# Sheet2.net
KiCad netlist of a schematic drawn in Altium Designer
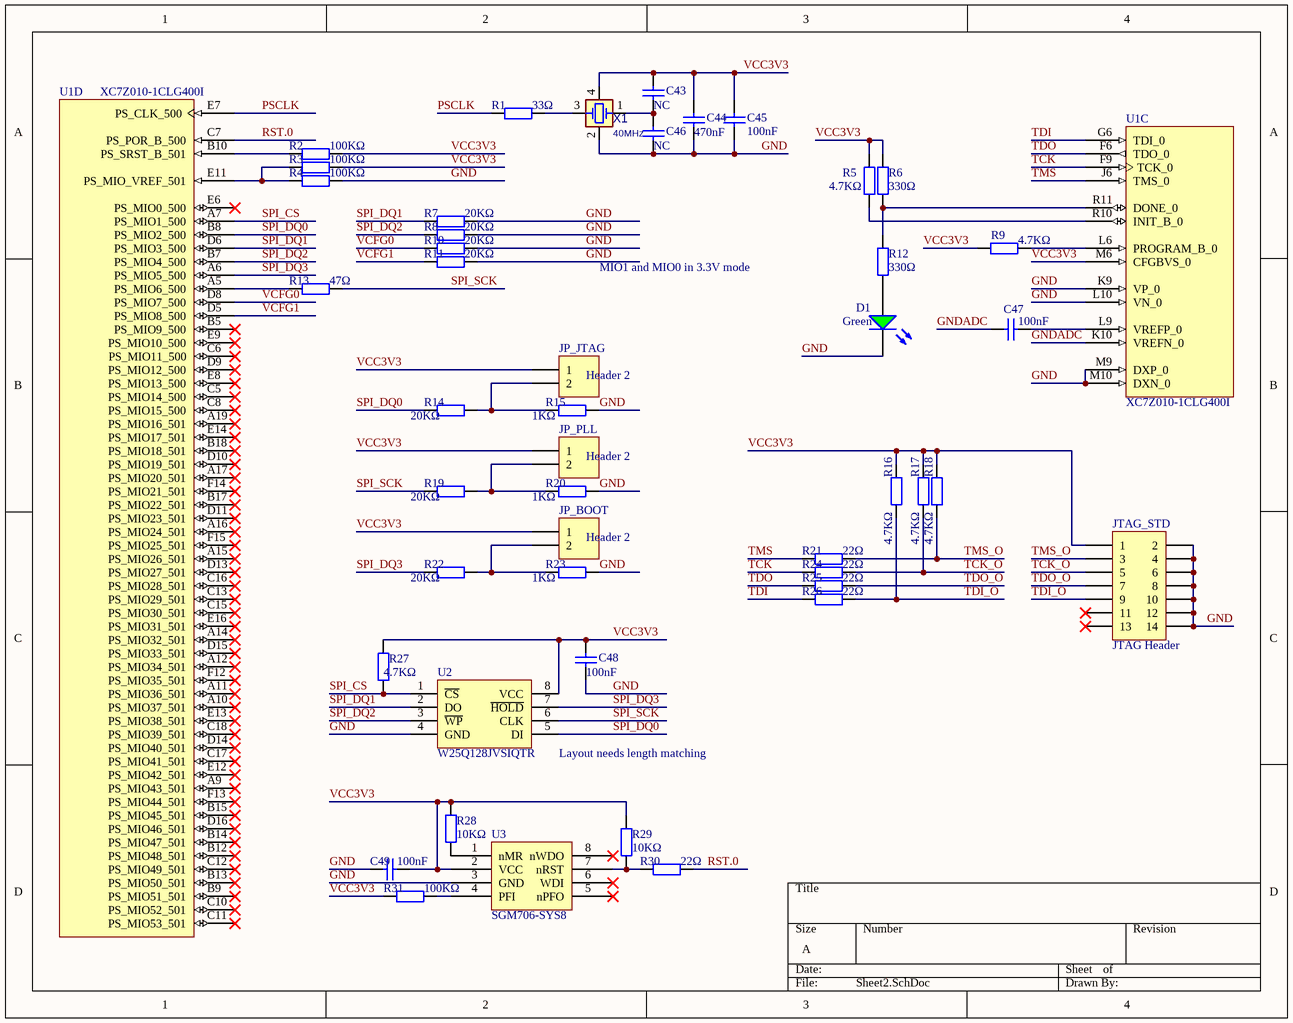
[diagram p0: Sheet2.SchDoc]

(export (version "E")
  (design (tool "Eeschema 10.0.6"))
  (components
    (comp (ref "C43")
      (value "NC")
      (footprint "0402_C")
      (description "贴片电容")
      (libsource (lib "Cap") (part "0402 470nF (474) 10% 10V"))
    )
    (comp (ref "C44")
      (value "470nF")
      (footprint "0402_C")
      (description "贴片电容")
      (libsource (lib "Cap") (part "0402 470nF (474) 10% 10V"))
    )
    (comp (ref "C45")
      (value "100nF")
      (footprint "1206_C")
      (description "贴片电容")
      (libsource (lib "Cap") (part "1206 100nF (104) 10% 50V"))
    )
    (comp (ref "C46")
      (value "NC")
      (footprint "0402_C")
      (description "贴片电容")
      (libsource (lib "Cap") (part "0402 470nF (474) 10% 10V"))
    )
    (comp (ref "C47")
      (value "100nF")
      (footprint "1206_C")
      (description "贴片电容")
      (libsource (lib "Cap") (part "1206 100nF (104) 10% 50V"))
    )
    (comp (ref "C48")
      (value "100nF")
      (footprint "1206_C")
      (description "贴片电容")
      (libsource (lib "Cap") (part "1206 100nF (104) 10% 50V"))
    )
    (comp (ref "C49")
      (value "100nF")
      (footprint "1206_C")
      (description "贴片电容")
      (libsource (lib "Cap") (part "1206 100nF (104) 10% 50V"))
    )
    (comp (ref "D1")
      (value "Green")
      (footprint "0805_LED_S1")
      (description "发光二极管")
      (libsource (lib "LED") (part "0805 翠绿"))
    )
    (comp (ref "JP_BOOT")
      (value "Header 2")
      (footprint "HDR1X2")
      (description "Header, 2-Pin")
      (fields (field (name "PUBLISHER") "Altium Limited"))
      (libsource (lib "Miscellaneous Connectors") (part "Header 2"))
    )
    (comp (ref "JP_JTAG")
      (value "Header 2")
      (footprint "HDR1X2")
      (description "Header, 2-Pin")
      (fields (field (name "PUBLISHER") "Altium Limited"))
      (libsource (lib "Miscellaneous Connectors") (part "Header 2"))
    )
    (comp (ref "JP_PLL")
      (value "Header 2")
      (footprint "HDR1X2")
      (description "Header, 2-Pin")
      (fields (field (name "PUBLISHER") "Altium Limited"))
      (libsource (lib "Miscellaneous Connectors") (part "Header 2"))
    )
    (comp (ref "JTAG_STD")
      (value "JTAG Header")
      (footprint "HDR2X7")
      (description "Header, 7-Pin, Dual row")
      (fields (field (name "PUBLISHER") "Altium Limited"))
      (libsource (lib "Miscellaneous Connectors") (part "Header 7X2"))
    )
    (comp (ref "R1")
      (value "33Ω")
      (footprint "0603_R")
      (description "贴片电阻")
      (libsource (lib "RES") (part "0603 33Ω (33R0) 1%"))
    )
    (comp (ref "R2")
      (value "100KΩ")
      (footprint "1206_R")
      (description "贴片电阻")
      (libsource (lib "RES") (part "1206 100KΩ (1003) 1%"))
    )
    (comp (ref "R3")
      (value "100KΩ")
      (footprint "1206_R")
      (description "贴片电阻")
      (libsource (lib "RES") (part "1206 100KΩ (1003) 1%"))
    )
    (comp (ref "R4")
      (value "100KΩ")
      (footprint "1206_R")
      (description "贴片电阻")
      (libsource (lib "RES") (part "1206 100KΩ (1003) 1%"))
    )
    (comp (ref "R5")
      (value "4.7KΩ")
      (footprint "1206_R")
      (description "贴片电阻")
      (libsource (lib "RES") (part "1206 4.7KΩ (4701) 1%"))
    )
    (comp (ref "R6")
      (value "330Ω")
      (footprint "0805_R")
      (description "贴片电阻")
      (libsource (lib "RES") (part "0805 330Ω (3300) 1%"))
    )
    (comp (ref "R7")
      (value "20KΩ")
      (footprint "0805_R")
      (description "贴片电阻")
      (libsource (lib "RES") (part "0805 20KΩ (2002) 1%"))
    )
    (comp (ref "R8")
      (value "20KΩ")
      (footprint "0805_R")
      (description "贴片电阻")
      (libsource (lib "RES") (part "0805 20KΩ (2002) 1%"))
    )
    (comp (ref "R9")
      (value "4.7KΩ")
      (footprint "1206_R")
      (description "贴片电阻")
      (libsource (lib "") (part "1206 4.7KΩ (4701) 1%_1"))
    )
    (comp (ref "R10")
      (value "20KΩ")
      (footprint "0805_R")
      (description "贴片电阻")
      (libsource (lib "RES") (part "0805 20KΩ (2002) 1%"))
    )
    (comp (ref "R11")
      (value "20KΩ")
      (footprint "0805_R")
      (description "贴片电阻")
      (libsource (lib "RES") (part "0805 20KΩ (2002) 1%"))
    )
    (comp (ref "R12")
      (value "330Ω")
      (footprint "0805_R")
      (description "贴片电阻")
      (libsource (lib "") (part "0805 330Ω (3300) 1%_1"))
    )
    (comp (ref "R13")
      (value "47Ω")
      (footprint "0805_R")
      (description "贴片电阻")
      (libsource (lib "RES") (part "0805 47Ω (47R0) 1%"))
    )
    (comp (ref "R14")
      (value "20KΩ")
      (footprint "0805_R")
      (description "贴片电阻")
      (libsource (lib "RES") (part "0805 20KΩ (2002) 1%"))
    )
    (comp (ref "R15")
      (value "1KΩ")
      (footprint "1206_R")
      (description "贴片电阻")
      (libsource (lib "RES") (part "1206 1KΩ (1001) 1%"))
    )
    (comp (ref "R16")
      (value "4.7KΩ")
      (footprint "1206_R")
      (description "贴片电阻")
      (libsource (lib "RES") (part "1206 4.7KΩ (4701) 1%"))
    )
    (comp (ref "R17")
      (value "4.7KΩ")
      (footprint "1206_R")
      (description "贴片电阻")
      (libsource (lib "RES") (part "1206 4.7KΩ (4701) 1%"))
    )
    (comp (ref "R18")
      (value "4.7KΩ")
      (footprint "1206_R")
      (description "贴片电阻")
      (libsource (lib "RES") (part "1206 4.7KΩ (4701) 1%"))
    )
    (comp (ref "R19")
      (value "20KΩ")
      (footprint "0805_R")
      (description "贴片电阻")
      (libsource (lib "RES") (part "0805 20KΩ (2002) 1%"))
    )
    (comp (ref "R20")
      (value "1KΩ")
      (footprint "1206_R")
      (description "贴片电阻")
      (libsource (lib "RES") (part "1206 1KΩ (1001) 1%"))
    )
    (comp (ref "R21")
      (value "22Ω")
      (footprint "1206_R")
      (description "贴片电阻")
      (libsource (lib "RES") (part "1206 22Ω (22R0) 1%"))
    )
    (comp (ref "R22")
      (value "20KΩ")
      (footprint "0805_R")
      (description "贴片电阻")
      (libsource (lib "RES") (part "0805 20KΩ (2002) 1%"))
    )
    (comp (ref "R23")
      (value "1KΩ")
      (footprint "1206_R")
      (description "贴片电阻")
      (libsource (lib "RES") (part "1206 1KΩ (1001) 1%"))
    )
    (comp (ref "R24")
      (value "22Ω")
      (footprint "1206_R")
      (description "贴片电阻")
      (libsource (lib "RES") (part "1206 22Ω (22R0) 1%"))
    )
    (comp (ref "R25")
      (value "22Ω")
      (footprint "1206_R")
      (description "贴片电阻")
      (libsource (lib "RES") (part "1206 22Ω (22R0) 1%"))
    )
    (comp (ref "R26")
      (value "22Ω")
      (footprint "1206_R")
      (description "贴片电阻")
      (libsource (lib "RES") (part "1206 22Ω (22R0) 1%"))
    )
    (comp (ref "R27")
      (value "4.7KΩ")
      (footprint "1206_R")
      (description "贴片电阻")
      (libsource (lib "RES") (part "1206 4.7KΩ (4701) 1%"))
    )
    (comp (ref "R28")
      (value "10KΩ")
      (footprint "1206_R")
      (description "贴片电阻")
      (libsource (lib "RES") (part "1206 10KΩ (1002) 1%"))
    )
    (comp (ref "R29")
      (value "10KΩ")
      (footprint "1206_R")
      (description "贴片电阻")
      (libsource (lib "RES") (part "1206 10KΩ (1002) 1%"))
    )
    (comp (ref "R30")
      (value "22Ω")
      (footprint "1206_R")
      (description "贴片电阻")
      (libsource (lib "RES") (part "1206 22Ω (22R0) 1%"))
    )
    (comp (ref "R31")
      (value "100KΩ")
      (footprint "1206_R")
      (description "贴片电阻")
      (libsource (lib "RES") (part "1206 100KΩ (1003) 1%"))
    )
    (comp (ref "U1")
      (value "XC7Z010-1CLG400I")
      (footprint "CLG400")
      (fields (field (name "GENERIC PART NUMBER") "XC7Z010") (field (name "MANUFACTURER") "Xilinx"))
      (libsource (lib "Xilinx Zynq-7000") (part "XC7Z010-1CLG400I"))
    )
    (comp (ref "U2")
      (value "W25Q128JVSIQTR")
      (footprint "SOIC-8_208mil")
      (description "Flash ROM")
      (libsource (lib "IC") (part "W25Q128JVSIQTR_[C97521]"))
    )
    (comp (ref "U3")
      (value "SGM706-SYS8")
      (footprint "SOIC-8_150mil")
      (description "MCU  Supervisor, 150mil SOP-8")
      (libsource (lib "IC") (part "EEPROM/AT24C256C-SSHL-T_[C6482]"))
    )
    (comp (ref "X1")
      (value "40MHz")
      (footprint "XTL_4_3225")
      (description "CRYSTAL 40.00 MHZ 4pF, 10PPM")
      (fields (field (name "MANF") "ABRACON") (field (name "MANF_P#") "ABM8W-40.0000MHZ-4-B1U-T3"))
      (libsource (lib "Crystal Oscillator") (part "XTL_4_40MHz_3225A"))
    )
  )
  (nets
    (net (code "1") (name "/GND") (class "Default")
      (node (ref "C44") (pin "2") (pinfunction "2_2") (pintype "passive"))
      (node (ref "C45") (pin "1") (pinfunction "1_1") (pintype "passive"))
      (node (ref "C46") (pin "2") (pinfunction "2_2") (pintype "passive"))
      (node (ref "C48") (pin "1") (pinfunction "1_1") (pintype "passive"))
      (node (ref "C49") (pin "1") (pinfunction "1_1") (pintype "passive"))
      (node (ref "D1") (pin "K") (pinfunction "K_K") (pintype "passive"))
      (node (ref "JTAG_STD") (pin "10") (pinfunction "10_10") (pintype "passive"))
      (node (ref "JTAG_STD") (pin "12") (pinfunction "12_12") (pintype "passive"))
      (node (ref "JTAG_STD") (pin "14") (pinfunction "14_14") (pintype "passive"))
      (node (ref "JTAG_STD") (pin "2") (pinfunction "2_2") (pintype "passive"))
      (node (ref "JTAG_STD") (pin "4") (pinfunction "4_4") (pintype "passive"))
      (node (ref "JTAG_STD") (pin "6") (pinfunction "6_6") (pintype "passive"))
      (node (ref "JTAG_STD") (pin "8") (pinfunction "8_8") (pintype "passive"))
      (node (ref "R10") (pin "2") (pinfunction "2_2") (pintype "passive"))
      (node (ref "R11") (pin "2") (pinfunction "2_2") (pintype "passive"))
      (node (ref "R15") (pin "2") (pinfunction "2_2") (pintype "passive"))
      (node (ref "R20") (pin "2") (pinfunction "2_2") (pintype "passive"))
      (node (ref "R23") (pin "2") (pinfunction "2_2") (pintype "passive"))
      (node (ref "R4") (pin "2") (pinfunction "2_2") (pintype "passive"))
      (node (ref "R7") (pin "2") (pinfunction "2_2") (pintype "passive"))
      (node (ref "R8") (pin "2") (pinfunction "2_2") (pintype "passive"))
      (node (ref "U1") (pin "K9") (pinfunction "VP_0_K9") (pintype "input"))
      (node (ref "U1") (pin "L10") (pinfunction "VN_0_L10") (pintype "input"))
      (node (ref "U1") (pin "M10") (pinfunction "DXN_0_M10") (pintype "input"))
      (node (ref "U1") (pin "M9") (pinfunction "DXP_0_M9") (pintype "input"))
      (node (ref "U2") (pin "4") (pinfunction "GND_4") (pintype "passive"))
      (node (ref "U3") (pin "3") (pinfunction "GND_3") (pintype "passive"))
      (node (ref "X1") (pin "2") (pinfunction "GND1_2") (pintype "passive"))
    )
    (net (code "2") (name "/GNDADC") (class "Default")
      (node (ref "C47") (pin "1") (pinfunction "1_1") (pintype "passive"))
      (node (ref "U1") (pin "K10") (pinfunction "VREFN_0_K10") (pintype "input"))
    )
    (net (code "3") (name "/PSCLK") (class "Default")
      (node (ref "R1") (pin "1") (pinfunction "1_1") (pintype "passive"))
      (node (ref "U1") (pin "E7") (pinfunction "PS_CLK_500_E7") (pintype "input"))
    )
    (net (code "4") (name "/RST.0") (class "Default")
      (node (ref "R30") (pin "2") (pinfunction "2_2") (pintype "passive"))
      (node (ref "U1") (pin "C7") (pinfunction "PS_POR_B_500_C7") (pintype "input"))
    )
    (net (code "5") (name "/SPI_CS") (class "Default")
      (node (ref "R27") (pin "1") (pinfunction "1_1") (pintype "passive"))
      (node (ref "U1") (pin "A7") (pinfunction "PS_MIO1_500_A7") (pintype "bidirectional"))
      (node (ref "U2") (pin "1") (pinfunction "~{CS}_1") (pintype "passive"))
    )
    (net (code "6") (name "/SPI_DQ0") (class "Default")
      (node (ref "R14") (pin "1") (pinfunction "1_1") (pintype "passive"))
      (node (ref "U1") (pin "B8") (pinfunction "PS_MIO2_500_B8") (pintype "bidirectional"))
      (node (ref "U2") (pin "5") (pinfunction "DI_5") (pintype "passive"))
    )
    (net (code "7") (name "/SPI_DQ1") (class "Default")
      (node (ref "R7") (pin "1") (pinfunction "1_1") (pintype "passive"))
      (node (ref "U1") (pin "D6") (pinfunction "PS_MIO3_500_D6") (pintype "bidirectional"))
      (node (ref "U2") (pin "2") (pinfunction "DO_2") (pintype "passive"))
    )
    (net (code "8") (name "/SPI_DQ2") (class "Default")
      (node (ref "R8") (pin "1") (pinfunction "1_1") (pintype "passive"))
      (node (ref "U1") (pin "B7") (pinfunction "PS_MIO4_500_B7") (pintype "bidirectional"))
      (node (ref "U2") (pin "3") (pinfunction "~{WP}_3") (pintype "passive"))
    )
    (net (code "9") (name "/SPI_DQ3") (class "Default")
      (node (ref "R22") (pin "1") (pinfunction "1_1") (pintype "passive"))
      (node (ref "U1") (pin "A6") (pinfunction "PS_MIO5_500_A6") (pintype "bidirectional"))
      (node (ref "U2") (pin "7") (pinfunction "~{HOLD}_7") (pintype "passive"))
    )
    (net (code "10") (name "/SPI_SCK") (class "Default")
      (node (ref "R13") (pin "2") (pinfunction "2_2") (pintype "passive"))
      (node (ref "R19") (pin "1") (pinfunction "1_1") (pintype "passive"))
      (node (ref "U2") (pin "6") (pinfunction "CLK_6") (pintype "passive"))
    )
    (net (code "11") (name "/TCK") (class "Default")
      (node (ref "R24") (pin "1") (pinfunction "1_1") (pintype "passive"))
      (node (ref "U1") (pin "F9") (pinfunction "TCK_0_F9") (pintype "input"))
    )
    (net (code "12") (name "/TCK_O") (class "Default")
      (node (ref "JTAG_STD") (pin "5") (pinfunction "5_5") (pintype "passive"))
      (node (ref "R17") (pin "1") (pinfunction "1_1") (pintype "passive"))
      (node (ref "R24") (pin "2") (pinfunction "2_2") (pintype "passive"))
    )
    (net (code "13") (name "/TDI") (class "Default")
      (node (ref "R26") (pin "1") (pinfunction "1_1") (pintype "passive"))
      (node (ref "U1") (pin "G6") (pinfunction "TDI_0_G6") (pintype "input"))
    )
    (net (code "14") (name "/TDI_O") (class "Default")
      (node (ref "JTAG_STD") (pin "9") (pinfunction "9_9") (pintype "passive"))
      (node (ref "R16") (pin "1") (pinfunction "1_1") (pintype "passive"))
      (node (ref "R26") (pin "2") (pinfunction "2_2") (pintype "passive"))
    )
    (net (code "15") (name "/TDO") (class "Default")
      (node (ref "R25") (pin "1") (pinfunction "1_1") (pintype "passive"))
      (node (ref "U1") (pin "F6") (pinfunction "TDO_0_F6") (pintype "output"))
    )
    (net (code "16") (name "/TDO_O") (class "Default")
      (node (ref "JTAG_STD") (pin "7") (pinfunction "7_7") (pintype "passive"))
      (node (ref "R25") (pin "2") (pinfunction "2_2") (pintype "passive"))
    )
    (net (code "17") (name "/TMS") (class "Default")
      (node (ref "R21") (pin "1") (pinfunction "1_1") (pintype "passive"))
      (node (ref "U1") (pin "J6") (pinfunction "TMS_0_J6") (pintype "input"))
    )
    (net (code "18") (name "/TMS_O") (class "Default")
      (node (ref "JTAG_STD") (pin "3") (pinfunction "3_3") (pintype "passive"))
      (node (ref "R18") (pin "1") (pinfunction "1_1") (pintype "passive"))
      (node (ref "R21") (pin "2") (pinfunction "2_2") (pintype "passive"))
    )
    (net (code "19") (name "/VCC3V3") (class "Default")
      (node (ref "C43") (pin "1") (pinfunction "1_1") (pintype "passive"))
      (node (ref "C44") (pin "1") (pinfunction "1_1") (pintype "passive"))
      (node (ref "C45") (pin "2") (pinfunction "2_2") (pintype "passive"))
      (node (ref "C48") (pin "2") (pinfunction "2_2") (pintype "passive"))
      (node (ref "C49") (pin "2") (pinfunction "2_2") (pintype "passive"))
      (node (ref "JP_BOOT") (pin "1") (pinfunction "1_1") (pintype "passive"))
      (node (ref "JP_JTAG") (pin "1") (pinfunction "1_1") (pintype "passive"))
      (node (ref "JP_PLL") (pin "1") (pinfunction "1_1") (pintype "passive"))
      (node (ref "JTAG_STD") (pin "1") (pinfunction "1_1") (pintype "passive"))
      (node (ref "R16") (pin "2") (pinfunction "2_2") (pintype "passive"))
      (node (ref "R17") (pin "2") (pinfunction "2_2") (pintype "passive"))
      (node (ref "R18") (pin "2") (pinfunction "2_2") (pintype "passive"))
      (node (ref "R2") (pin "2") (pinfunction "2_2") (pintype "passive"))
      (node (ref "R27") (pin "2") (pinfunction "2_2") (pintype "passive"))
      (node (ref "R28") (pin "2") (pinfunction "2_2") (pintype "passive"))
      (node (ref "R29") (pin "2") (pinfunction "2_2") (pintype "passive"))
      (node (ref "R3") (pin "2") (pinfunction "2_2") (pintype "passive"))
      (node (ref "R31") (pin "1") (pinfunction "1_1") (pintype "passive"))
      (node (ref "R5") (pin "2") (pinfunction "2_2") (pintype "passive"))
      (node (ref "R6") (pin "1") (pinfunction "1_1") (pintype "passive"))
      (node (ref "R9") (pin "1") (pinfunction "1_1") (pintype "passive"))
      (node (ref "U1") (pin "M6") (pinfunction "CFGBVS_0_M6") (pintype "input"))
      (node (ref "U2") (pin "8") (pinfunction "VCC_8") (pintype "passive"))
      (node (ref "U3") (pin "2") (pinfunction "VCC_2") (pintype "passive"))
      (node (ref "X1") (pin "4") (pinfunction "GND2_4") (pintype "passive"))
    )
    (net (code "20") (name "/VCFG0") (class "Default")
      (node (ref "R10") (pin "1") (pinfunction "1_1") (pintype "passive"))
      (node (ref "U1") (pin "D8") (pinfunction "PS_MIO7_500_D8") (pintype "bidirectional"))
    )
    (net (code "21") (name "/VCFG1") (class "Default")
      (node (ref "R11") (pin "1") (pinfunction "1_1") (pintype "passive"))
      (node (ref "U1") (pin "D5") (pinfunction "PS_MIO8_500_D5") (pintype "bidirectional"))
    )
    (net (code "22") (name "Net-(D1-PadA)") (class "Default")
      (node (ref "D1") (pin "A") (pinfunction "A_A") (pintype "passive"))
      (node (ref "R12") (pin "1") (pinfunction "1_1") (pintype "passive"))
    )
    (net (code "23") (name "Net-(JP_BOOT-Pad2)") (class "Default")
      (node (ref "JP_BOOT") (pin "2") (pinfunction "2_2") (pintype "passive"))
      (node (ref "R22") (pin "2") (pinfunction "2_2") (pintype "passive"))
      (node (ref "R23") (pin "1") (pinfunction "1_1") (pintype "passive"))
    )
    (net (code "24") (name "Net-(JP_JTAG-Pad2)") (class "Default")
      (node (ref "JP_JTAG") (pin "2") (pinfunction "2_2") (pintype "passive"))
      (node (ref "R14") (pin "2") (pinfunction "2_2") (pintype "passive"))
      (node (ref "R15") (pin "1") (pinfunction "1_1") (pintype "passive"))
    )
    (net (code "25") (name "Net-(JP_PLL-Pad2)") (class "Default")
      (node (ref "JP_PLL") (pin "2") (pinfunction "2_2") (pintype "passive"))
      (node (ref "R19") (pin "2") (pinfunction "2_2") (pintype "passive"))
      (node (ref "R20") (pin "1") (pinfunction "1_1") (pintype "passive"))
    )
    (net (code "26") (name "Net-(U1C-DONE_0)") (class "Default")
      (node (ref "R12") (pin "2") (pinfunction "2_2") (pintype "passive"))
      (node (ref "R6") (pin "2") (pinfunction "2_2") (pintype "passive"))
      (node (ref "U1") (pin "R11") (pinfunction "DONE_0_R11") (pintype "bidirectional"))
    )
    (net (code "27") (name "Net-(U1C-INIT_B_0)") (class "Default")
      (node (ref "R5") (pin "1") (pinfunction "1_1") (pintype "passive"))
      (node (ref "U1") (pin "R10") (pinfunction "INIT_B_0_R10") (pintype "bidirectional"))
    )
    (net (code "28") (name "Net-(U1C-PROGRAM_B_0)") (class "Default")
      (node (ref "R9") (pin "2") (pinfunction "2_2") (pintype "passive"))
      (node (ref "U1") (pin "L6") (pinfunction "PROGRAM_B_0_L6") (pintype "input"))
    )
    (net (code "29") (name "Net-(U1C-VREFP_0)") (class "Default")
      (node (ref "C47") (pin "2") (pinfunction "2_2") (pintype "passive"))
      (node (ref "U1") (pin "L9") (pinfunction "VREFP_0_L9") (pintype "input"))
    )
    (net (code "30") (name "Net-(U1D-PS_MIO6_500)") (class "Default")
      (node (ref "R13") (pin "1") (pinfunction "1_1") (pintype "passive"))
      (node (ref "U1") (pin "A5") (pinfunction "PS_MIO6_500_A5") (pintype "bidirectional"))
    )
    (net (code "31") (name "Net-(U1D-PS_MIO_VREF_501)") (class "Default")
      (node (ref "R3") (pin "1") (pinfunction "1_1") (pintype "passive"))
      (node (ref "R4") (pin "1") (pinfunction "1_1") (pintype "passive"))
      (node (ref "U1") (pin "E11") (pinfunction "PS_MIO_VREF_501_E11") (pintype "input"))
    )
    (net (code "32") (name "Net-(U1D-PS_SRST_B_501)") (class "Default")
      (node (ref "R2") (pin "1") (pinfunction "1_1") (pintype "passive"))
      (node (ref "U1") (pin "B10") (pinfunction "PS_SRST_B_501_B10") (pintype "input"))
    )
    (net (code "33") (name "Net-(U3-PFI)") (class "Default")
      (node (ref "R31") (pin "2") (pinfunction "2_2") (pintype "passive"))
      (node (ref "U3") (pin "4") (pinfunction "PFI_4") (pintype "passive"))
    )
    (net (code "34") (name "Net-(U3-nMR)") (class "Default")
      (node (ref "R28") (pin "1") (pinfunction "1_1") (pintype "passive"))
      (node (ref "U3") (pin "1") (pinfunction "nMR_1") (pintype "passive"))
    )
    (net (code "35") (name "Net-(U3-nRST)") (class "Default")
      (node (ref "R29") (pin "1") (pinfunction "1_1") (pintype "passive"))
      (node (ref "R30") (pin "1") (pinfunction "1_1") (pintype "passive"))
      (node (ref "U3") (pin "7") (pinfunction "nRST_7") (pintype "passive"))
    )
    (net (code "36") (name "Net-(X1-XA)") (class "Default")
      (node (ref "C43") (pin "2") (pinfunction "2_2") (pintype "passive"))
      (node (ref "C46") (pin "1") (pinfunction "1_1") (pintype "passive"))
      (node (ref "X1") (pin "1") (pinfunction "XA_1") (pintype "passive"))
    )
    (net (code "37") (name "Net-(X1-XB)") (class "Default")
      (node (ref "R1") (pin "2") (pinfunction "2_2") (pintype "passive"))
      (node (ref "X1") (pin "3") (pinfunction "XB_3") (pintype "passive"))
    )
    (net (code "38") (name "unconnected-(JTAG_STD-Pad11)") (class "Default")
      (node (ref "JTAG_STD") (pin "11") (pinfunction "11_11") (pintype "passive+no_connect"))
    )
    (net (code "39") (name "unconnected-(JTAG_STD-Pad13)") (class "Default")
      (node (ref "JTAG_STD") (pin "13") (pinfunction "13_13") (pintype "passive+no_connect"))
    )
    (net (code "40") (name "unconnected-(U1D-PS_MIO0_500-PadE6)") (class "Default")
      (node (ref "U1") (pin "E6") (pinfunction "PS_MIO0_500_E6") (pintype "bidirectional+no_connect"))
    )
    (net (code "41") (name "unconnected-(U1D-PS_MIO9_500-PadB5)") (class "Default")
      (node (ref "U1") (pin "B5") (pinfunction "PS_MIO9_500_B5") (pintype "bidirectional+no_connect"))
    )
    (net (code "42") (name "unconnected-(U1D-PS_MIO10_500-PadE9)") (class "Default")
      (node (ref "U1") (pin "E9") (pinfunction "PS_MIO10_500_E9") (pintype "bidirectional+no_connect"))
    )
    (net (code "43") (name "unconnected-(U1D-PS_MIO11_500-PadC6)") (class "Default")
      (node (ref "U1") (pin "C6") (pinfunction "PS_MIO11_500_C6") (pintype "bidirectional+no_connect"))
    )
    (net (code "44") (name "unconnected-(U1D-PS_MIO12_500-PadD9)") (class "Default")
      (node (ref "U1") (pin "D9") (pinfunction "PS_MIO12_500_D9") (pintype "bidirectional+no_connect"))
    )
    (net (code "45") (name "unconnected-(U1D-PS_MIO13_500-PadE8)") (class "Default")
      (node (ref "U1") (pin "E8") (pinfunction "PS_MIO13_500_E8") (pintype "bidirectional+no_connect"))
    )
    (net (code "46") (name "unconnected-(U1D-PS_MIO14_500-PadC5)") (class "Default")
      (node (ref "U1") (pin "C5") (pinfunction "PS_MIO14_500_C5") (pintype "bidirectional+no_connect"))
    )
    (net (code "47") (name "unconnected-(U1D-PS_MIO15_500-PadC8)") (class "Default")
      (node (ref "U1") (pin "C8") (pinfunction "PS_MIO15_500_C8") (pintype "bidirectional+no_connect"))
    )
    (net (code "48") (name "unconnected-(U1D-PS_MIO16_501-PadA19)") (class "Default")
      (node (ref "U1") (pin "A19") (pinfunction "PS_MIO16_501_A19") (pintype "bidirectional+no_connect"))
    )
    (net (code "49") (name "unconnected-(U1D-PS_MIO17_501-PadE14)") (class "Default")
      (node (ref "U1") (pin "E14") (pinfunction "PS_MIO17_501_E14") (pintype "bidirectional+no_connect"))
    )
    (net (code "50") (name "unconnected-(U1D-PS_MIO18_501-PadB18)") (class "Default")
      (node (ref "U1") (pin "B18") (pinfunction "PS_MIO18_501_B18") (pintype "bidirectional+no_connect"))
    )
    (net (code "51") (name "unconnected-(U1D-PS_MIO19_501-PadD10)") (class "Default")
      (node (ref "U1") (pin "D10") (pinfunction "PS_MIO19_501_D10") (pintype "bidirectional+no_connect"))
    )
    (net (code "52") (name "unconnected-(U1D-PS_MIO20_501-PadA17)") (class "Default")
      (node (ref "U1") (pin "A17") (pinfunction "PS_MIO20_501_A17") (pintype "bidirectional+no_connect"))
    )
    (net (code "53") (name "unconnected-(U1D-PS_MIO21_501-PadF14)") (class "Default")
      (node (ref "U1") (pin "F14") (pinfunction "PS_MIO21_501_F14") (pintype "bidirectional+no_connect"))
    )
    (net (code "54") (name "unconnected-(U1D-PS_MIO22_501-PadB17)") (class "Default")
      (node (ref "U1") (pin "B17") (pinfunction "PS_MIO22_501_B17") (pintype "bidirectional+no_connect"))
    )
    (net (code "55") (name "unconnected-(U1D-PS_MIO23_501-PadD11)") (class "Default")
      (node (ref "U1") (pin "D11") (pinfunction "PS_MIO23_501_D11") (pintype "bidirectional+no_connect"))
    )
    (net (code "56") (name "unconnected-(U1D-PS_MIO24_501-PadA16)") (class "Default")
      (node (ref "U1") (pin "A16") (pinfunction "PS_MIO24_501_A16") (pintype "bidirectional+no_connect"))
    )
    (net (code "57") (name "unconnected-(U1D-PS_MIO25_501-PadF15)") (class "Default")
      (node (ref "U1") (pin "F15") (pinfunction "PS_MIO25_501_F15") (pintype "bidirectional+no_connect"))
    )
    (net (code "58") (name "unconnected-(U1D-PS_MIO26_501-PadA15)") (class "Default")
      (node (ref "U1") (pin "A15") (pinfunction "PS_MIO26_501_A15") (pintype "bidirectional+no_connect"))
    )
    (net (code "59") (name "unconnected-(U1D-PS_MIO27_501-PadD13)") (class "Default")
      (node (ref "U1") (pin "D13") (pinfunction "PS_MIO27_501_D13") (pintype "bidirectional+no_connect"))
    )
    (net (code "60") (name "unconnected-(U1D-PS_MIO28_501-PadC16)") (class "Default")
      (node (ref "U1") (pin "C16") (pinfunction "PS_MIO28_501_C16") (pintype "bidirectional+no_connect"))
    )
    (net (code "61") (name "unconnected-(U1D-PS_MIO29_501-PadC13)") (class "Default")
      (node (ref "U1") (pin "C13") (pinfunction "PS_MIO29_501_C13") (pintype "bidirectional+no_connect"))
    )
    (net (code "62") (name "unconnected-(U1D-PS_MIO30_501-PadC15)") (class "Default")
      (node (ref "U1") (pin "C15") (pinfunction "PS_MIO30_501_C15") (pintype "bidirectional+no_connect"))
    )
    (net (code "63") (name "unconnected-(U1D-PS_MIO31_501-PadE16)") (class "Default")
      (node (ref "U1") (pin "E16") (pinfunction "PS_MIO31_501_E16") (pintype "bidirectional+no_connect"))
    )
    (net (code "64") (name "unconnected-(U1D-PS_MIO32_501-PadA14)") (class "Default")
      (node (ref "U1") (pin "A14") (pinfunction "PS_MIO32_501_A14") (pintype "bidirectional+no_connect"))
    )
    (net (code "65") (name "unconnected-(U1D-PS_MIO33_501-PadD15)") (class "Default")
      (node (ref "U1") (pin "D15") (pinfunction "PS_MIO33_501_D15") (pintype "bidirectional+no_connect"))
    )
    (net (code "66") (name "unconnected-(U1D-PS_MIO34_501-PadA12)") (class "Default")
      (node (ref "U1") (pin "A12") (pinfunction "PS_MIO34_501_A12") (pintype "bidirectional+no_connect"))
    )
    (net (code "67") (name "unconnected-(U1D-PS_MIO35_501-PadF12)") (class "Default")
      (node (ref "U1") (pin "F12") (pinfunction "PS_MIO35_501_F12") (pintype "bidirectional+no_connect"))
    )
    (net (code "68") (name "unconnected-(U1D-PS_MIO36_501-PadA11)") (class "Default")
      (node (ref "U1") (pin "A11") (pinfunction "PS_MIO36_501_A11") (pintype "bidirectional+no_connect"))
    )
    (net (code "69") (name "unconnected-(U1D-PS_MIO37_501-PadA10)") (class "Default")
      (node (ref "U1") (pin "A10") (pinfunction "PS_MIO37_501_A10") (pintype "bidirectional+no_connect"))
    )
    (net (code "70") (name "unconnected-(U1D-PS_MIO38_501-PadE13)") (class "Default")
      (node (ref "U1") (pin "E13") (pinfunction "PS_MIO38_501_E13") (pintype "bidirectional+no_connect"))
    )
    (net (code "71") (name "unconnected-(U1D-PS_MIO39_501-PadC18)") (class "Default")
      (node (ref "U1") (pin "C18") (pinfunction "PS_MIO39_501_C18") (pintype "bidirectional+no_connect"))
    )
    (net (code "72") (name "unconnected-(U1D-PS_MIO40_501-PadD14)") (class "Default")
      (node (ref "U1") (pin "D14") (pinfunction "PS_MIO40_501_D14") (pintype "bidirectional+no_connect"))
    )
    (net (code "73") (name "unconnected-(U1D-PS_MIO41_501-PadC17)") (class "Default")
      (node (ref "U1") (pin "C17") (pinfunction "PS_MIO41_501_C17") (pintype "bidirectional+no_connect"))
    )
    (net (code "74") (name "unconnected-(U1D-PS_MIO42_501-PadE12)") (class "Default")
      (node (ref "U1") (pin "E12") (pinfunction "PS_MIO42_501_E12") (pintype "bidirectional+no_connect"))
    )
    (net (code "75") (name "unconnected-(U1D-PS_MIO43_501-PadA9)") (class "Default")
      (node (ref "U1") (pin "A9") (pinfunction "PS_MIO43_501_A9") (pintype "bidirectional+no_connect"))
    )
    (net (code "76") (name "unconnected-(U1D-PS_MIO44_501-PadF13)") (class "Default")
      (node (ref "U1") (pin "F13") (pinfunction "PS_MIO44_501_F13") (pintype "bidirectional+no_connect"))
    )
    (net (code "77") (name "unconnected-(U1D-PS_MIO45_501-PadB15)") (class "Default")
      (node (ref "U1") (pin "B15") (pinfunction "PS_MIO45_501_B15") (pintype "bidirectional+no_connect"))
    )
    (net (code "78") (name "unconnected-(U1D-PS_MIO46_501-PadD16)") (class "Default")
      (node (ref "U1") (pin "D16") (pinfunction "PS_MIO46_501_D16") (pintype "bidirectional+no_connect"))
    )
    (net (code "79") (name "unconnected-(U1D-PS_MIO47_501-PadB14)") (class "Default")
      (node (ref "U1") (pin "B14") (pinfunction "PS_MIO47_501_B14") (pintype "bidirectional+no_connect"))
    )
    (net (code "80") (name "unconnected-(U1D-PS_MIO48_501-PadB12)") (class "Default")
      (node (ref "U1") (pin "B12") (pinfunction "PS_MIO48_501_B12") (pintype "bidirectional+no_connect"))
    )
    (net (code "81") (name "unconnected-(U1D-PS_MIO49_501-PadC12)") (class "Default")
      (node (ref "U1") (pin "C12") (pinfunction "PS_MIO49_501_C12") (pintype "bidirectional+no_connect"))
    )
    (net (code "82") (name "unconnected-(U1D-PS_MIO50_501-PadB13)") (class "Default")
      (node (ref "U1") (pin "B13") (pinfunction "PS_MIO50_501_B13") (pintype "bidirectional+no_connect"))
    )
    (net (code "83") (name "unconnected-(U1D-PS_MIO51_501-PadB9)") (class "Default")
      (node (ref "U1") (pin "B9") (pinfunction "PS_MIO51_501_B9") (pintype "bidirectional+no_connect"))
    )
    (net (code "84") (name "unconnected-(U1D-PS_MIO52_501-PadC10)") (class "Default")
      (node (ref "U1") (pin "C10") (pinfunction "PS_MIO52_501_C10") (pintype "bidirectional+no_connect"))
    )
    (net (code "85") (name "unconnected-(U1D-PS_MIO53_501-PadC11)") (class "Default")
      (node (ref "U1") (pin "C11") (pinfunction "PS_MIO53_501_C11") (pintype "bidirectional+no_connect"))
    )
    (net (code "86") (name "unconnected-(U3-WDI-Pad6)") (class "Default")
      (node (ref "U3") (pin "6") (pinfunction "WDI_6") (pintype "passive+no_connect"))
    )
    (net (code "87") (name "unconnected-(U3-nPFO-Pad5)") (class "Default")
      (node (ref "U3") (pin "5") (pinfunction "nPFO_5") (pintype "passive+no_connect"))
    )
    (net (code "88") (name "unconnected-(U3-nWDO-Pad8)") (class "Default")
      (node (ref "U3") (pin "8") (pinfunction "nWDO_8") (pintype "passive+no_connect"))
    )
  )
)
